# MPPT.net
KiCad netlist of a schematic drawn in Altium Designer
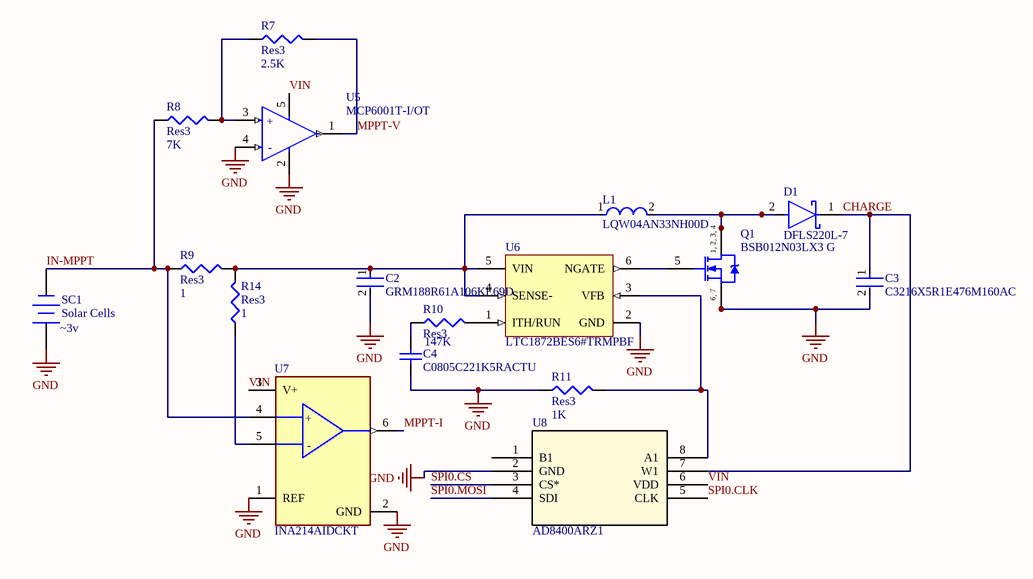
[diagram p0: MPPT.SchDoc]

(export (version "E")
  (design (tool "Eeschema 10.0.6"))
  (components
    (comp (ref "C2")
      (value "GRM188R61A106KE69D")
      (footprint "FP-GRM18-0_15-MFG")
      (description "CAP CER 10UF 10V X5R 0603")
      (fields
        (field (name "OCTOPART") "https://octopart.com/grm188r61a106ke69d-murata-22851381")
        (field (name "MANUFACTURER") "Murata")
      )
      (libsource (lib "Altium Content Vault") (part "11868f565c42a9108669ba33697ecf6"))
    )
    (comp (ref "C3")
      (value "C3216X5R1E476M160AC")
      (footprint "FP-C3216-160-MFG")
      (description "CAP CER 47UF 25V X5R 1206")
      (fields (field (name "3DS PART NUMBER") "220-00004") (field (name "VOLTAGE") "25V"))
      (libsource (lib "Altium Content Vault") (part "11868f565c42a9108669ba33697ecf6"))
    )
    (comp (ref "C4")
      (value "C0805C221K5RACTU")
      (footprint "CAPC2013X88X50LL20T25")
      (fields (field (name "MANUFACTURER") "Kemet"))
      (libsource (lib "Altium Content Vault") (part "CAP"))
    )
    (comp (ref "D1")
      (value "DFLS220L-7")
      (footprint "FP-PowerDI123-MFG")
      (description "DIODE SCHOTTKY 20V 2A POWERDI123")
      (fields
        (field (name "MANUFACTURER") "Diodes Inc.")
        (field (name "OCTOPART") "https://octopart.com/dfls220l-7-diodes+inc.-328575")
      )
      (libsource (lib "Altium Content Vault") (part "1d6ec82d83fb6aee721767c19dac4b9"))
    )
    (comp (ref "L1")
      (value "LQW04AN33NH00D")
      (footprint "FP-LQW04AN_00-MFG")
      (description "Wire Wound RF Inductor 33nH ±3% 140mA 1.11Ω 03015 (0804)")
      (fields (field (name "TOLERANCE") "3%"))
      (libsource (lib "Altium Content Vault") (part "725321dda6339637d4d059423bc1c3c"))
    )
    (comp (ref "Q1")
      (value "BSB012N03LX3 G")
      (footprint "INF-MG-WDSON-2-8_V")
      (description "N-Channel OptiMOS 3 Power-MOSFET, 30 V VDS, 180 A ID, -40 to 150 degC, MG-WDSON-2-8, Reel, Green")
      (fields (field (name "MANUFACTURER") "Infineon"))
      (libsource (lib "Altium Content Vault") (part "INF-NEMOS-DDDDGSS-WDSON-7"))
    )
    (comp (ref "R7")
      (value "Res3")
      (footprint "J1-0603")
      (description "Resistor")
      (fields (field (name "ALTIUM_VALUE") "2.5K") (field (name "PUBLISHER") "Altium Limited"))
      (libsource (lib "Miscellaneous Devices") (part "Res3"))
    )
    (comp (ref "R8")
      (value "Res3")
      (footprint "J1-0603")
      (description "Resistor")
      (fields (field (name "ALTIUM_VALUE") "7K") (field (name "PUBLISHER") "Altium Limited"))
      (libsource (lib "Miscellaneous Devices") (part "Res3"))
    )
    (comp (ref "R9")
      (value "Res3")
      (footprint "J1-0603")
      (description "Resistor")
      (fields (field (name "ALTIUM_VALUE") "1") (field (name "PUBLISHER") "Altium Limited"))
      (libsource (lib "Miscellaneous Devices") (part "Res3"))
    )
    (comp (ref "R10")
      (value "Res3")
      (footprint "J1-0603")
      (description "Resistor")
      (fields (field (name "ALTIUM_VALUE") "147K") (field (name "PUBLISHER") "Altium Limited"))
      (libsource (lib "Miscellaneous Devices") (part "Res3"))
    )
    (comp (ref "R11")
      (value "Res3")
      (footprint "J1-0603")
      (description "Resistor")
      (fields (field (name "ALTIUM_VALUE") "1K") (field (name "PUBLISHER") "Altium Limited"))
      (libsource (lib "Miscellaneous Devices") (part "Res3"))
    )
    (comp (ref "R14")
      (value "Res3")
      (footprint "J1-0603")
      (description "Resistor")
      (fields (field (name "ALTIUM_VALUE") "1") (field (name "PUBLISHER") "Altium Limited"))
      (libsource (lib "Miscellaneous Devices") (part "Res3"))
    )
    (comp (ref "SC1")
      (value "Solar Cells")
      (footprint "BAT-2")
      (description "Multicell Battery")
      (fields (field (name "PUBLISHER") "Altium Limited"))
      (libsource (lib "Miscellaneous Devices") (part "Battery"))
    )
    (comp (ref "U5")
      (value "MCP6001T-I/OT")
      (footprint "FP-C04-091-OT-IPC_A")
      (description "IC OPAMP GP 1 CIRCUIT SOT23-5")
      (fields (field (name "VOLTAGE") "6V"))
      (libsource (lib "Altium Content Vault") (part "c8a8c153b9e84e05c1733c8ea85bdd9"))
    )
    (comp (ref "U6")
      (value "LTC1872BES6#TRMPBF")
      (footprint "LT-S6-6-TSOT-23_L")
      (fields (field (name "MANUFACTURER") "Linear Technology"))
      (libsource (lib "Altium Content Vault") (part "LT-LTC1872X-S6-6"))
    )
    (comp (ref "U7")
      (value "INA214AIDCKT")
      (footprint "FP-DCK0006A-MFG")
      (description "IC CURR SENSE 1 CIRCUIT SC70-6")
      (fields
        (field (name "MANUFACTURER") "Texas Instruments")
        (field (name "OCTOPART") "https://octopart.com/ina214aidckt-texas+instruments-7830703")
      )
      (libsource (lib "Altium Content Vault") (part "c10d82c028949ab116d50aa41bcba86"))
    )
    (comp (ref "U8")
      (value "AD8400ARZ1")
      (footprint "R_8_ADI")
      (description "No Description Available")
      (fields (field (name "COPYRIGHT") "Copyright (C) 2018 Accelerated Designs. All rights reserved"))
      (libsource (lib "2021-05-17_02-47-14") (part "AD8400ARZ1"))
    )
  )
  (nets
    (net (code "1") (name "/CHARGE") (class "Default")
      (node (ref "C3") (pin "1") (pinfunction "1_1") (pintype "passive"))
      (node (ref "D1") (pin "1") (pinfunction "C_1") (pintype "passive"))
      (node (ref "U8") (pin "7") (pinfunction "W1_7") (pintype "passive"))
    )
    (net (code "2") (name "/IN-MPPT") (class "Default")
      (node (ref "R8") (pin "1") (pinfunction "1_1") (pintype "passive"))
      (node (ref "R9") (pin "1") (pinfunction "1_1") (pintype "passive"))
      (node (ref "SC1") (pin "2") (pinfunction "-_2") (pintype "passive"))
      (node (ref "U7") (pin "4") (pinfunction "IN+_4") (pintype "tri_state"))
    )
    (net (code "3") (name "/MPPT-I") (class "Default")
      (node (ref "U7") (pin "6") (pinfunction "OUT_6") (pintype "output"))
    )
    (net (code "4") (name "/MPPT-V") (class "Default")
      (node (ref "R7") (pin "2") (pinfunction "2_2") (pintype "passive"))
      (node (ref "U5") (pin "1") (pinfunction "VOUT_1") (pintype "output"))
    )
    (net (code "5") (name "/SPI0.CLK") (class "Default")
      (node (ref "U8") (pin "5") (pinfunction "CLK_5") (pintype "passive"))
    )
    (net (code "6") (name "/SPI0.CS") (class "Default")
      (node (ref "U8") (pin "3") (pinfunction "CS*_3") (pintype "passive"))
    )
    (net (code "7") (name "/SPI0.MOSI") (class "Default")
      (node (ref "U8") (pin "4") (pinfunction "SDI_4") (pintype "passive"))
    )
    (net (code "8") (name "/VIN") (class "Default")
      (node (ref "U5") (pin "5") (pinfunction "VDD_5") (pintype "power_in"))
      (node (ref "U7") (pin "3") (pinfunction "V+_3") (pintype "power_in"))
      (node (ref "U8") (pin "6") (pinfunction "VDD_6") (pintype "power_in"))
    )
    (net (code "9") (name "GND") (class "Default")
      (node (ref "C2") (pin "2") (pinfunction "2_2") (pintype "passive"))
      (node (ref "C3") (pin "2") (pinfunction "2_2") (pintype "passive"))
      (node (ref "C4") (pin "1") (pinfunction "1_1") (pintype "passive"))
      (node (ref "Q1") (pin "6") (pinfunction "SOURCE_6") (pintype "passive"))
      (node (ref "Q1") (pin "7") (pinfunction "SOURCE_7") (pintype "passive"))
      (node (ref "R11") (pin "1") (pinfunction "1_1") (pintype "passive"))
      (node (ref "SC1") (pin "1") (pinfunction "+_1") (pintype "passive"))
      (node (ref "U5") (pin "2") (pinfunction "VSS_2") (pintype "power_in"))
      (node (ref "U5") (pin "4") (pinfunction "VIN-_4") (pintype "input"))
      (node (ref "U6") (pin "2") (pinfunction "GND_2") (pintype "power_in"))
      (node (ref "U7") (pin "1") (pinfunction "REF_1") (pintype "passive"))
      (node (ref "U7") (pin "2") (pinfunction "GND_2") (pintype "power_in"))
      (node (ref "U8") (pin "2") (pinfunction "GND_2") (pintype "passive"))
    )
    (net (code "10") (name "Net-(C4-Pad2)") (class "Default")
      (node (ref "C4") (pin "2") (pinfunction "2_2") (pintype "passive"))
      (node (ref "R10") (pin "1") (pinfunction "1_1") (pintype "passive"))
    )
    (net (code "11") (name "Net-(D1-A)") (class "Default")
      (node (ref "D1") (pin "2") (pinfunction "A_2") (pintype "passive"))
      (node (ref "L1") (pin "2") (pinfunction "2_2") (pintype "passive"))
      (node (ref "Q1") (pin "1") (pinfunction "DRAIN_1") (pintype "passive"))
      (node (ref "Q1") (pin "2") (pinfunction "DRAIN_2") (pintype "passive"))
      (node (ref "Q1") (pin "3") (pinfunction "DRAIN_3") (pintype "passive"))
      (node (ref "Q1") (pin "4") (pinfunction "DRAIN_4") (pintype "passive"))
    )
    (net (code "12") (name "Net-(Q1-GATE)") (class "Default")
      (node (ref "Q1") (pin "5") (pinfunction "GATE_5") (pintype "passive"))
      (node (ref "U6") (pin "6") (pinfunction "NGATE_6") (pintype "output"))
    )
    (net (code "13") (name "Net-(U5-VIN+)") (class "Default")
      (node (ref "R7") (pin "1") (pinfunction "1_1") (pintype "passive"))
      (node (ref "R8") (pin "2") (pinfunction "2_2") (pintype "passive"))
      (node (ref "U5") (pin "3") (pinfunction "VIN+_3") (pintype "input"))
    )
    (net (code "14") (name "Net-(U6-ITH{slash}RUN)") (class "Default")
      (node (ref "R10") (pin "2") (pinfunction "2_2") (pintype "passive"))
      (node (ref "U6") (pin "1") (pinfunction "ITH/RUN_1") (pintype "input"))
    )
    (net (code "15") (name "Net-(U6-SENSE-)") (class "Default")
      (node (ref "C2") (pin "1") (pinfunction "1_1") (pintype "passive"))
      (node (ref "L1") (pin "1") (pinfunction "1_1") (pintype "passive"))
      (node (ref "R14") (pin "2") (pinfunction "2_2") (pintype "passive"))
      (node (ref "R9") (pin "2") (pinfunction "2_2") (pintype "passive"))
      (node (ref "U6") (pin "4") (pinfunction "SENSE-_4") (pintype "input"))
      (node (ref "U6") (pin "5") (pinfunction "VIN_5") (pintype "power_in"))
    )
    (net (code "16") (name "Net-(U6-VFB)") (class "Default")
      (node (ref "R11") (pin "2") (pinfunction "2_2") (pintype "passive"))
      (node (ref "U6") (pin "3") (pinfunction "VFB_3") (pintype "input"))
      (node (ref "U8") (pin "8") (pinfunction "A1_8") (pintype "passive"))
    )
    (net (code "17") (name "Net-(U7-IN-)") (class "Default")
      (node (ref "R14") (pin "1") (pinfunction "1_1") (pintype "passive"))
      (node (ref "U7") (pin "5") (pinfunction "IN-_5") (pintype "tri_state"))
    )
    (net (code "18") (name "unconnected-(U8-B1-Pad1)") (class "Default")
      (node (ref "U8") (pin "1") (pinfunction "B1_1") (pintype "passive"))
    )
  )
)
